# MSSRP-BATT.net
KiCad netlist of a schematic drawn in EAGLE
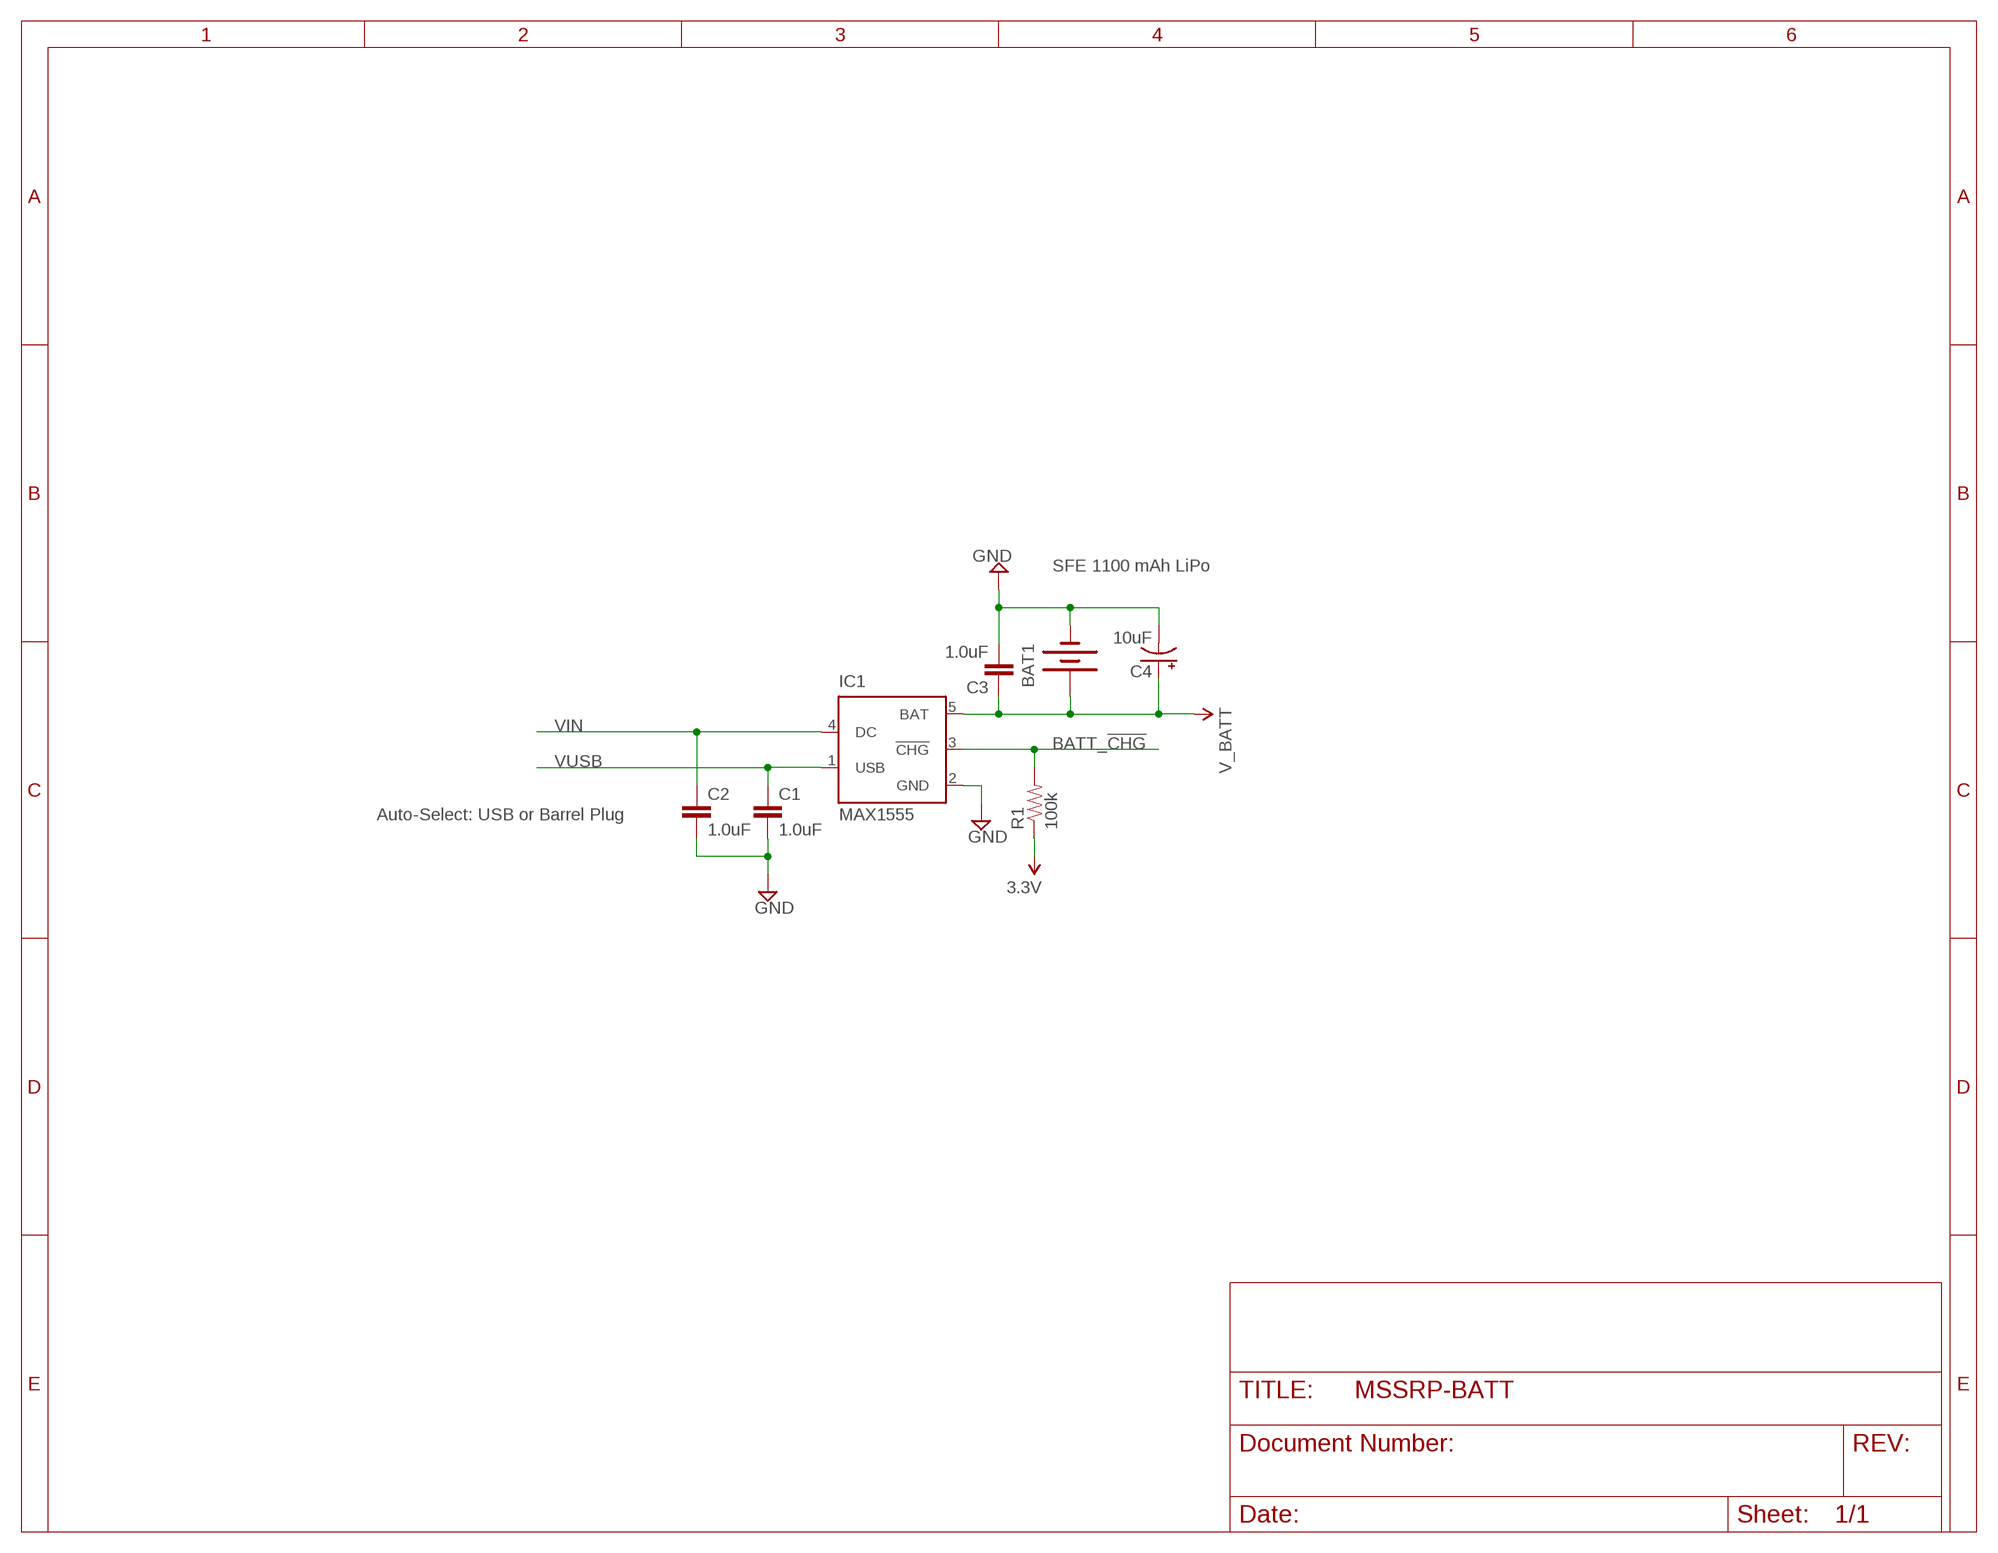
[diagram p0: schematic, sheet 1]

(export (version "E")
  (design (tool "Eeschema 10.0.6"))
  (components
    (comp (ref "BAT1")
      (value "BATTERY1100")
      (footprint "eagle-import:LIPO-1100MAH")
      (libsource (lib "eagle-import") (part "BATTERY1100"))
    )
    (comp (ref "C1")
      (value "1.0uF")
      (footprint "eagle-import:0603-CAP")
      (libsource (lib "eagle-import") (part "1.0UF-16V-10%(0603)"))
    )
    (comp (ref "C2")
      (value "1.0uF")
      (footprint "eagle-import:0603-CAP")
      (libsource (lib "eagle-import") (part "1.0UF-16V-10%(0603)"))
    )
    (comp (ref "C3")
      (value "1.0uF")
      (footprint "eagle-import:0603-CAP")
      (libsource (lib "eagle-import") (part "1.0UF-16V-10%(0603)"))
    )
    (comp (ref "C4")
      (value "10uF")
      (footprint "eagle-import:EIA3216")
      (libsource (lib "eagle-import") (part "10UF-16V-10%(TANT)"))
    )
    (comp (ref "IC1")
      (value "MAX1555")
      (footprint "eagle-import:SOT23-5L")
      (fields (field (name "MF") "MAXIM") (field (name "MPN") "MAX1555EZK+T"))
      (libsource (lib "eagle-import") (part "MAX1555"))
    )
    (comp (ref "R1")
      (value "100k")
      (footprint "eagle-import:0603-RES")
      (libsource (lib "eagle-import") (part "100KOHM1/10W1%(0603)"))
    )
  )
  (nets
    (net (code "1") (name "/BATT_~{CHG}") (class "Default")
      (node (ref "IC1") (pin "3") (pinfunction "~{CHG}_3") (pintype "output"))
      (node (ref "R1") (pin "2") (pinfunction "2_2") (pintype "passive"))
    )
    (net (code "2") (name "/VIN") (class "Default")
      (node (ref "C2") (pin "1") (pinfunction "1_1") (pintype "passive"))
      (node (ref "IC1") (pin "4") (pinfunction "DC_4") (pintype "input"))
    )
    (net (code "3") (name "/VUSB") (class "Default")
      (node (ref "C1") (pin "1") (pinfunction "1_1") (pintype "passive"))
      (node (ref "IC1") (pin "1") (pinfunction "USB_1") (pintype "input"))
    )
    (net (code "4") (name "3.3V") (class "Default")
      (node (ref "R1") (pin "1") (pinfunction "1_1") (pintype "passive"))
    )
    (net (code "5") (name "GND") (class "Default")
      (node (ref "BAT1") (pin "-") (pinfunction "-_-") (pintype "power_in"))
      (node (ref "C1") (pin "2") (pinfunction "2_2") (pintype "passive"))
      (node (ref "C2") (pin "2") (pinfunction "2_2") (pintype "passive"))
      (node (ref "C3") (pin "2") (pinfunction "2_2") (pintype "passive"))
      (node (ref "C4") (pin "C") (pinfunction "-_C") (pintype "passive"))
      (node (ref "IC1") (pin "2") (pinfunction "GND_2") (pintype "power_in"))
    )
    (net (code "6") (name "V_BATT") (class "Default")
      (node (ref "BAT1") (pin "+") (pinfunction "+_+") (pintype "power_in"))
      (node (ref "C3") (pin "1") (pinfunction "1_1") (pintype "passive"))
      (node (ref "C4") (pin "A") (pinfunction "+_A") (pintype "passive"))
      (node (ref "IC1") (pin "5") (pinfunction "BAT_5") (pintype "passive"))
    )
  )
)
